# 2015_PerfServos.net
KiCad netlist of a schematic drawn in Altium Designer
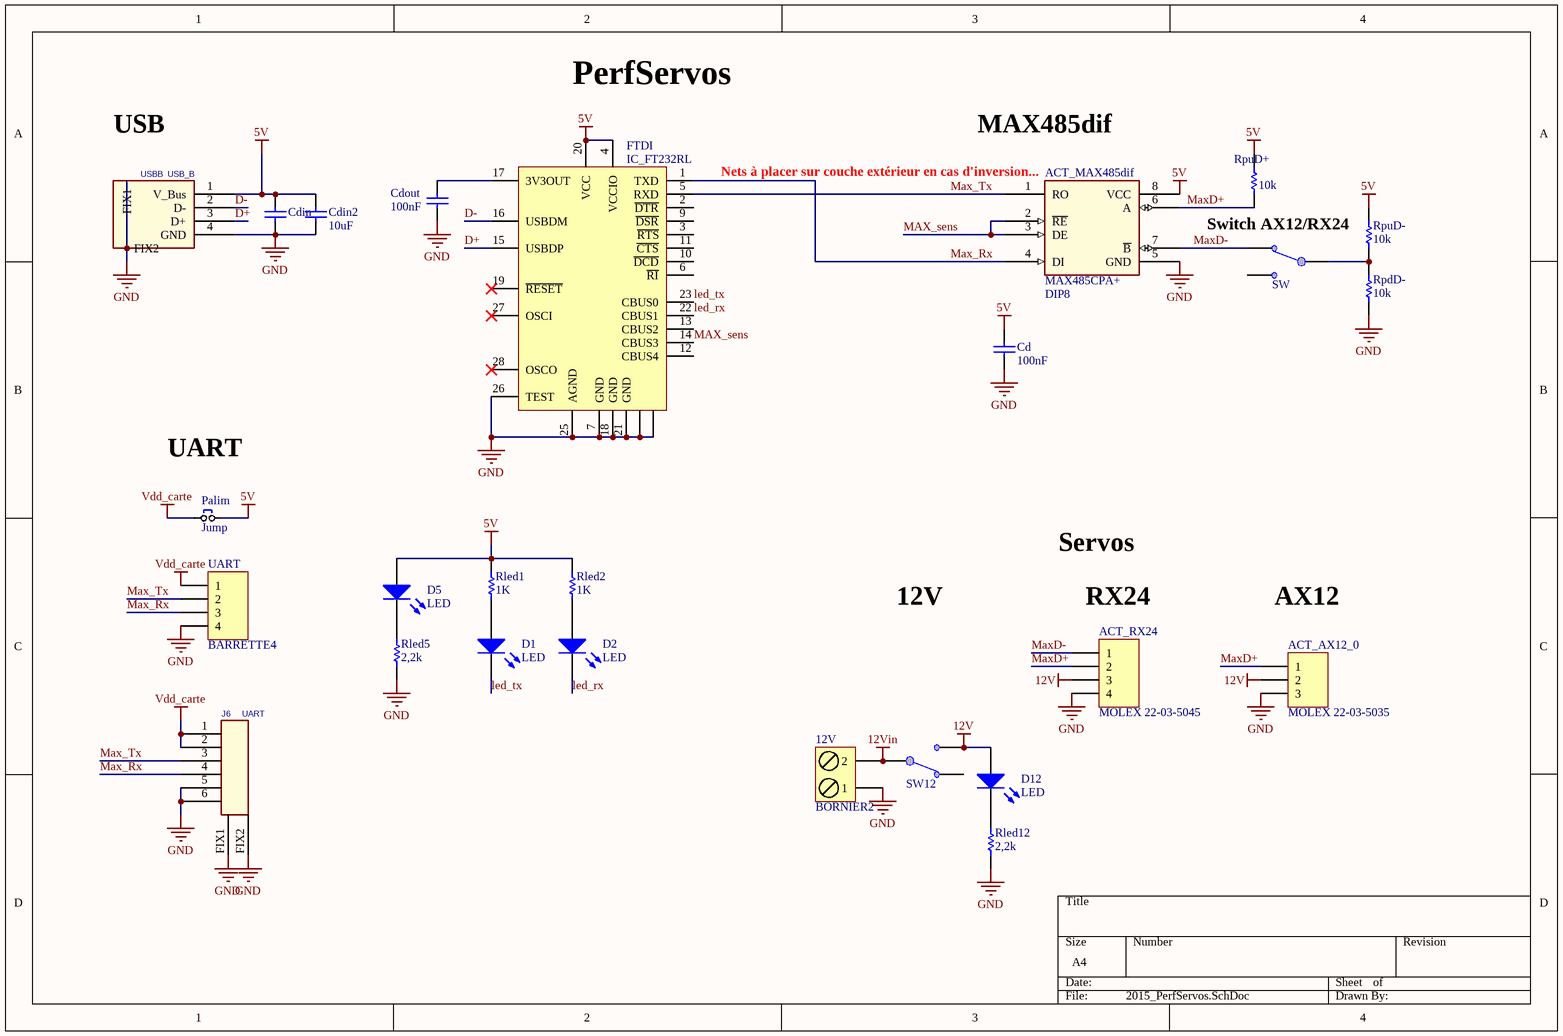
[diagram p0: 2015_PerfServos.SchDoc]

(export (version "E")
  (design (tool "Eeschema 10.0.6"))
  (components
    (comp (ref "12V")
      (value "BORNIER2")
      (footprint "BORNIER_2V_5.08MM")
      (description "Terminal blocks, 2 pins, pitch=5mm")
      (libsource (lib "Connecteur") (part "BORNIER2"))
    )
    (comp (ref "ACT_AX12_0")
      (value "MOLEX 22-03-5035")
      (footprint "MOLEX3_2.5MM")
      (description "Header, 3-Pin")
      (fields (field (name "PUBLISHER") "Altium Limited"))
      (libsource (lib "Connecteur") (part "BARRETTE3"))
    )
    (comp (ref "ACT_MAX485dif")
      (value "MAX485CPA+_DIP8")
      (footprint "SO8_N")
      (description "EMETTEUR/RECEPTEUR FAIBLE PUISSANCE DE LIAISONS RS422/RS485 - DIP8")
      (fields (field (name "TYPE") "MAX485CPA+") (field (name "PACKAGE") "DIP8"))
      (libsource (lib "circuits integres") (part "MAX485CPA+_DIP8"))
    )
    (comp (ref "ACT_RX24")
      (value "MOLEX 22-03-5045")
      (footprint "MOLEX4_2.5MM")
      (description "Header, 4-Pin")
      (fields (field (name "PUBLISHER") "Altium Limited"))
      (libsource (lib "Connecteur") (part "BARRETTE4"))
    )
    (comp (ref "Cd")
      (value "100nF")
      (footprint "C0805_N")
      (description "Capacitor")
      (fields (field (name "PUBLISHER") "Altium Limited"))
      (libsource (lib "_ROBOT") (part "Condensateur"))
    )
    (comp (ref "Cdin")
      (value "100nF")
      (footprint "C0603_N")
      (description "Capacitor")
      (fields (field (name "PUBLISHER") "Damien GUITTON"))
      (libsource (lib "") (part "Capacitor_1"))
    )
    (comp (ref "Cdin2")
      (value "10uF")
      (footprint "C1206_N")
      (description "Capacitor")
      (fields (field (name "PUBLISHER") "Altium Limited"))
      (libsource (lib "DG_Condensateur") (part "Capacitor"))
    )
    (comp (ref "Cdout")
      (value "100nF")
      (footprint "C0603_N")
      (description "Capacitor")
      (fields (field (name "PUBLISHER") "Damien GUITTON"))
      (libsource (lib "DG_discret") (part "Capacitor"))
    )
    (comp (ref "D1")
      (value "LED")
      (footprint "LED_0805")
      (description "Typical LED")
      (fields (field (name "PUBLISHER") "Altium Limited"))
      (libsource (lib "DG_LED") (part "LED"))
    )
    (comp (ref "D2")
      (value "LED")
      (footprint "LED_0805")
      (description "Typical LED")
      (fields (field (name "PUBLISHER") "Altium Limited"))
      (libsource (lib "DG_LED") (part "LED"))
    )
    (comp (ref "D5")
      (value "LED")
      (footprint "LED_0805")
      (description "Typical LED")
      (fields (field (name "PUBLISHER") "Altium Limited"))
      (libsource (lib "DG_LED") (part "LED"))
    )
    (comp (ref "D12")
      (value "LED")
      (footprint "LED_0805")
      (description "Typical LED")
      (fields (field (name "PUBLISHER") "Altium Limited"))
      (libsource (lib "DG_LED") (part "LED"))
    )
    (comp (ref "FTDI")
      (value "IC_FT232RL")
      (footprint "SSOP28_N")
      (description "FT232R USB UART")
      (libsource (lib "Circuit intégré") (part "IC_FT232RL"))
    )
    (comp (ref "J6") (value "UART") (footprint "RJ11_6/6") (libsource (lib "*") (part "CONNECTEUR_RJ12")))
    (comp (ref "Palim")
      (value "Jump")
      (footprint "HDR1X2")
      (description "Jumper SIP2.54")
      (libsource (lib "Connecteur") (part "Jumper SIP2.54"))
    )
    (comp (ref "Rled1")
      (value "1K")
      (footprint "R1206_N")
      (description "Resistor")
      (fields (field (name "PUBLISHER") "Altium Limited"))
      (libsource (lib "DG_Resistance") (part "Resistor"))
    )
    (comp (ref "Rled2")
      (value "1K")
      (footprint "R1206_N")
      (description "Resistor")
      (fields (field (name "PUBLISHER") "Altium Limited"))
      (libsource (lib "DG_Resistance") (part "Resistor"))
    )
    (comp (ref "Rled5")
      (value "2,2k")
      (footprint "R1206_N")
      (description "Resistor")
      (fields (field (name "PUBLISHER") "Altium Limited"))
      (libsource (lib "DG_Resistance") (part "Resistor"))
    )
    (comp (ref "Rled12")
      (value "2,2k")
      (footprint "R1206_N")
      (description "Resistor")
      (fields (field (name "PUBLISHER") "Altium Limited"))
      (libsource (lib "DG_Resistance") (part "Resistor"))
    )
    (comp (ref "RpdD-")
      (value "10k")
      (footprint "R1206_N")
      (description "Resistor")
      (fields (field (name "PUBLISHER") "Altium Limited"))
      (libsource (lib "_ROBOT") (part "Resistor"))
    )
    (comp (ref "RpuD+")
      (value "10k")
      (footprint "R1206_N")
      (description "Resistor")
      (fields (field (name "PUBLISHER") "Altium Limited"))
      (libsource (lib "_ROBOT") (part "Resistor"))
    )
    (comp (ref "RpuD-")
      (value "10k")
      (footprint "R1206_N")
      (description "Resistor")
      (fields (field (name "PUBLISHER") "Altium Limited"))
      (libsource (lib "_ROBOT") (part "Resistor"))
    )
    (comp (ref "SW")
      (value "~")
      (footprint "SW_UNIPOL_DROIT - Ebay - SPDT - 11x6x5")
      (description "Switch unipolaire a levier")
      (libsource (lib "_ROBOT") (part "SW SPDT- APEM Série 523x"))
    )
    (comp (ref "SW12")
      (value "~")
      (footprint "SW_UNIPOL_DROIT - Ebay - SPDT - 11x6x5")
      (description "Switch unipolaire a levier")
      (libsource (lib "_ROBOT") (part "SW SPDT- APEM Série 523x"))
    )
    (comp (ref "UART")
      (value "BARRETTE4")
      (footprint "HDR1X4")
      (description "Header, 4-Pin")
      (fields (field (name "PUBLISHER") "Altium Limited"))
      (libsource (lib "Connecteur") (part "HDR1X4"))
    )
    (comp (ref "USBB") (value "USB_B") (footprint "USB_B_COUDE") (libsource (lib "*") (part "USB_B")))
  )
  (nets
    (net (code "1") (name "/D+") (class "Default")
      (node (ref "FTDI") (pin "15") (pinfunction "USBDP_15") (pintype "passive"))
      (node (ref "USBB") (pin "3") (pinfunction "D+_3") (pintype "passive"))
    )
    (net (code "2") (name "/D-") (class "Default")
      (node (ref "FTDI") (pin "16") (pinfunction "USBDM_16") (pintype "passive"))
      (node (ref "USBB") (pin "2") (pinfunction "D-_2") (pintype "passive"))
    )
    (net (code "3") (name "/MAX_sens") (class "Default")
      (node (ref "ACT_MAX485dif") (pin "2") (pinfunction "~{RE}_2") (pintype "input"))
      (node (ref "ACT_MAX485dif") (pin "3") (pinfunction "DE_3") (pintype "input"))
      (node (ref "FTDI") (pin "14") (pinfunction "CBUS3_14") (pintype "passive"))
    )
    (net (code "4") (name "/MaxD+") (class "Default")
      (node (ref "ACT_AX12_0") (pin "1") (pinfunction "1_1") (pintype "passive"))
      (node (ref "ACT_MAX485dif") (pin "6") (pinfunction "A_6") (pintype "bidirectional"))
      (node (ref "ACT_RX24") (pin "2") (pinfunction "2_2") (pintype "passive"))
      (node (ref "RpuD+") (pin "1") (pinfunction "1_1") (pintype "passive"))
    )
    (net (code "5") (name "/MaxD-") (class "Default")
      (node (ref "ACT_MAX485dif") (pin "7") (pinfunction "~{B}_7") (pintype "bidirectional"))
      (node (ref "ACT_RX24") (pin "1") (pinfunction "1_1") (pintype "passive"))
      (node (ref "SW") (pin "NC1") (pinfunction "NC1_NC1") (pintype "passive"))
    )
    (net (code "6") (name "/Max_Rx") (class "Default")
      (node (ref "ACT_MAX485dif") (pin "4") (pinfunction "DI_4") (pintype "input"))
      (node (ref "FTDI") (pin "1") (pinfunction "TXD_1") (pintype "passive"))
      (node (ref "J6") (pin "4") (pinfunction "4_4") (pintype "passive"))
      (node (ref "UART") (pin "3") (pinfunction "3_3") (pintype "passive"))
    )
    (net (code "7") (name "/Max_Tx") (class "Default")
      (node (ref "ACT_MAX485dif") (pin "1") (pinfunction "RO_1") (pintype "tri_state"))
      (node (ref "FTDI") (pin "5") (pinfunction "RXD_5") (pintype "passive"))
      (node (ref "J6") (pin "3") (pinfunction "3_3") (pintype "passive"))
      (node (ref "UART") (pin "2") (pinfunction "2_2") (pintype "passive"))
    )
    (net (code "8") (name "/led_rx") (class "Default")
      (node (ref "D2") (pin "2") (pinfunction "2_2") (pintype "passive"))
      (node (ref "FTDI") (pin "22") (pinfunction "CBUS1_22") (pintype "passive"))
    )
    (net (code "9") (name "/led_tx") (class "Default")
      (node (ref "D1") (pin "2") (pinfunction "2_2") (pintype "passive"))
      (node (ref "FTDI") (pin "23") (pinfunction "CBUS0_23") (pintype "passive"))
    )
    (net (code "10") (name "5V") (class "Default")
      (node (ref "ACT_MAX485dif") (pin "8") (pinfunction "VCC_8") (pintype "passive"))
      (node (ref "Cd") (pin "2") (pinfunction "2_2") (pintype "passive"))
      (node (ref "Cdin") (pin "2") (pinfunction "2_2") (pintype "passive"))
      (node (ref "Cdin2") (pin "2") (pinfunction "2_2") (pintype "passive"))
      (node (ref "D5") (pin "1") (pinfunction "1_1") (pintype "passive"))
      (node (ref "FTDI") (pin "20") (pinfunction "VCC_20") (pintype "passive"))
      (node (ref "FTDI") (pin "4") (pinfunction "VCCIO_4") (pintype "passive"))
      (node (ref "Palim") (pin "2") (pinfunction "2_2") (pintype "passive"))
      (node (ref "Rled1") (pin "2") (pinfunction "2_2") (pintype "passive"))
      (node (ref "Rled2") (pin "2") (pinfunction "2_2") (pintype "passive"))
      (node (ref "RpuD+") (pin "2") (pinfunction "2_2") (pintype "passive"))
      (node (ref "RpuD-") (pin "1") (pinfunction "1_1") (pintype "passive"))
      (node (ref "USBB") (pin "1") (pinfunction "V_Bus_1") (pintype "passive"))
    )
    (net (code "11") (name "12V") (class "Default")
      (node (ref "ACT_AX12_0") (pin "2") (pinfunction "2_2") (pintype "passive"))
      (node (ref "ACT_RX24") (pin "3") (pinfunction "3_3") (pintype "passive"))
      (node (ref "D12") (pin "1") (pinfunction "1_1") (pintype "passive"))
      (node (ref "SW12") (pin "NO1") (pinfunction "NO1_NO1") (pintype "passive"))
    )
    (net (code "12") (name "12Vin") (class "Default")
      (node (ref "12V") (pin "2") (pinfunction "2_2") (pintype "passive"))
      (node (ref "SW12") (pin "COMMON1") (pinfunction "COMMON1_COMMON1") (pintype "passive"))
    )
    (net (code "13") (name "GND") (class "Default")
      (node (ref "12V") (pin "1") (pinfunction "1_1") (pintype "passive"))
      (node (ref "ACT_AX12_0") (pin "3") (pinfunction "3_3") (pintype "passive"))
      (node (ref "ACT_MAX485dif") (pin "5") (pinfunction "GND_5") (pintype "passive"))
      (node (ref "ACT_RX24") (pin "4") (pinfunction "4_4") (pintype "passive"))
      (node (ref "Cd") (pin "1") (pinfunction "1_1") (pintype "passive"))
      (node (ref "Cdin") (pin "1") (pinfunction "1_1") (pintype "passive"))
      (node (ref "Cdin2") (pin "1") (pinfunction "1_1") (pintype "passive"))
      (node (ref "Cdout") (pin "1") (pinfunction "1_1") (pintype "passive"))
      (node (ref "FTDI") (pin "18") (pinfunction "GND_18") (pintype "passive"))
      (node (ref "FTDI") (pin "21") (pinfunction "GND_21") (pintype "passive"))
      (node (ref "FTDI") (pin "24") (pinfunction "NC_24") (pintype "passive"))
      (node (ref "FTDI") (pin "25") (pinfunction "AGND_25") (pintype "passive"))
      (node (ref "FTDI") (pin "26") (pinfunction "TEST_26") (pintype "passive"))
      (node (ref "FTDI") (pin "7") (pinfunction "GND_7") (pintype "passive"))
      (node (ref "FTDI") (pin "8") (pinfunction "NC_8") (pintype "passive"))
      (node (ref "J6") (pin "5") (pinfunction "5_5") (pintype "passive"))
      (node (ref "J6") (pin "6") (pinfunction "6_6") (pintype "passive"))
      (node (ref "J6") (pin "FIX1") (pinfunction "FIX1_FIX1") (pintype "passive"))
      (node (ref "J6") (pin "FIX2") (pinfunction "FIX2_FIX2") (pintype "passive"))
      (node (ref "Rled12") (pin "1") (pinfunction "1_1") (pintype "passive"))
      (node (ref "Rled5") (pin "1") (pinfunction "1_1") (pintype "passive"))
      (node (ref "RpdD-") (pin "2") (pinfunction "2_2") (pintype "passive"))
      (node (ref "UART") (pin "4") (pinfunction "4_4") (pintype "passive"))
      (node (ref "USBB") (pin "4") (pinfunction "GND_4") (pintype "passive"))
      (node (ref "USBB") (pin "FIX1") (pinfunction "FIX1_FIX1") (pintype "passive"))
      (node (ref "USBB") (pin "FIX2") (pinfunction "FIX2_FIX2") (pintype "passive"))
    )
    (net (code "14") (name "Net-(D1-Pad1)") (class "Default")
      (node (ref "D1") (pin "1") (pinfunction "1_1") (pintype "passive"))
      (node (ref "Rled1") (pin "1") (pinfunction "1_1") (pintype "passive"))
    )
    (net (code "15") (name "Net-(D2-Pad1)") (class "Default")
      (node (ref "D2") (pin "1") (pinfunction "1_1") (pintype "passive"))
      (node (ref "Rled2") (pin "1") (pinfunction "1_1") (pintype "passive"))
    )
    (net (code "16") (name "Net-(D5-Pad2)") (class "Default")
      (node (ref "D5") (pin "2") (pinfunction "2_2") (pintype "passive"))
      (node (ref "Rled5") (pin "2") (pinfunction "2_2") (pintype "passive"))
    )
    (net (code "17") (name "Net-(D12-Pad2)") (class "Default")
      (node (ref "D12") (pin "2") (pinfunction "2_2") (pintype "passive"))
      (node (ref "Rled12") (pin "2") (pinfunction "2_2") (pintype "passive"))
    )
    (net (code "18") (name "Net-(FTDI-3V3OUT)") (class "Default")
      (node (ref "Cdout") (pin "2") (pinfunction "2_2") (pintype "passive"))
      (node (ref "FTDI") (pin "17") (pinfunction "3V3OUT_17") (pintype "passive"))
    )
    (net (code "19") (name "Net-(RpdD--Pad1)") (class "Default")
      (node (ref "RpdD-") (pin "1") (pinfunction "1_1") (pintype "passive"))
      (node (ref "RpuD-") (pin "2") (pinfunction "2_2") (pintype "passive"))
      (node (ref "SW") (pin "COMMON1") (pinfunction "COMMON1_COMMON1") (pintype "passive"))
    )
    (net (code "20") (name "Vdd_carte") (class "Default")
      (node (ref "J6") (pin "1") (pinfunction "1_1") (pintype "passive"))
      (node (ref "J6") (pin "2") (pinfunction "2_2") (pintype "passive"))
      (node (ref "Palim") (pin "1") (pinfunction "1_1") (pintype "passive"))
      (node (ref "UART") (pin "1") (pinfunction "1_1") (pintype "passive"))
    )
    (net (code "21") (name "unconnected-(FTDI-CBUS2-Pad13)") (class "Default")
      (node (ref "FTDI") (pin "13") (pinfunction "CBUS2_13") (pintype "passive"))
    )
    (net (code "22") (name "unconnected-(FTDI-CBUS4-Pad12)") (class "Default")
      (node (ref "FTDI") (pin "12") (pinfunction "CBUS4_12") (pintype "passive"))
    )
    (net (code "23") (name "unconnected-(FTDI-OSCI-Pad27)") (class "Default")
      (node (ref "FTDI") (pin "27") (pinfunction "OSCI_27") (pintype "passive+no_connect"))
    )
    (net (code "24") (name "unconnected-(FTDI-OSCO-Pad28)") (class "Default")
      (node (ref "FTDI") (pin "28") (pinfunction "OSCO_28") (pintype "passive+no_connect"))
    )
    (net (code "25") (name "unconnected-(FTDI-~{CTS}-Pad11)") (class "Default")
      (node (ref "FTDI") (pin "11") (pinfunction "~{CTS}_11") (pintype "passive"))
    )
    (net (code "26") (name "unconnected-(FTDI-~{DCD}-Pad10)") (class "Default")
      (node (ref "FTDI") (pin "10") (pinfunction "~{DCD}_10") (pintype "passive"))
    )
    (net (code "27") (name "unconnected-(FTDI-~{DSR}-Pad9)") (class "Default")
      (node (ref "FTDI") (pin "9") (pinfunction "~{DSR}_9") (pintype "passive"))
    )
    (net (code "28") (name "unconnected-(FTDI-~{DTR}-Pad2)") (class "Default")
      (node (ref "FTDI") (pin "2") (pinfunction "~{DTR}_2") (pintype "passive"))
    )
    (net (code "29") (name "unconnected-(FTDI-~{RESET}-Pad19)") (class "Default")
      (node (ref "FTDI") (pin "19") (pinfunction "~{RESET}_19") (pintype "passive+no_connect"))
    )
    (net (code "30") (name "unconnected-(FTDI-~{RI}-Pad6)") (class "Default")
      (node (ref "FTDI") (pin "6") (pinfunction "~{RI}_6") (pintype "passive"))
    )
    (net (code "31") (name "unconnected-(FTDI-~{RTS}-Pad3)") (class "Default")
      (node (ref "FTDI") (pin "3") (pinfunction "~{RTS}_3") (pintype "passive"))
    )
    (net (code "32") (name "unconnected-(SW-PadNO1)") (class "Default")
      (node (ref "SW") (pin "NO1") (pinfunction "NO1_NO1") (pintype "passive"))
    )
    (net (code "33") (name "unconnected-(SW12-PadNC1)") (class "Default")
      (node (ref "SW12") (pin "NC1") (pinfunction "NC1_NC1") (pintype "passive"))
    )
  )
)
